# 18f45502.net
KiCad netlist of a schematic drawn in EAGLE
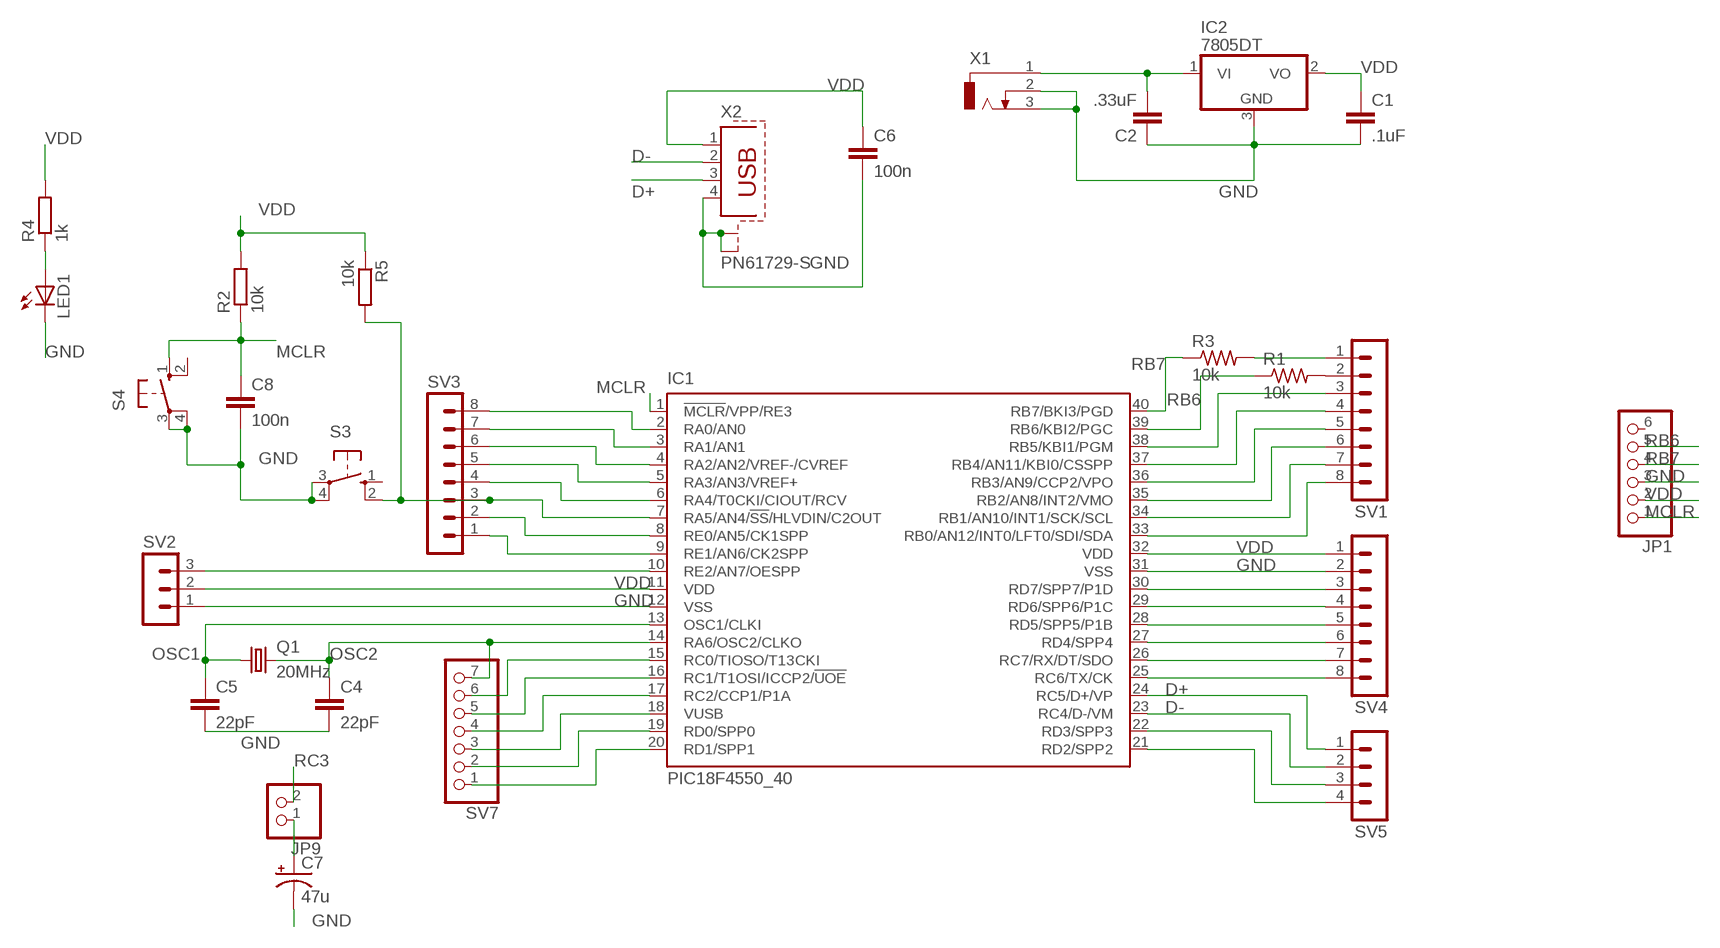
[diagram p0: schematic, sheet 1]

(export (version "E")
  (design (tool "Eeschema 10.0.6"))
  (components
    (comp (ref "C1")
      (value ".1uF")
      (footprint "eagle-import:C0805K")
      (libsource (lib "eagle-import") (part "C-EUC0805K"))
    )
    (comp (ref "C2")
      (value ".33uF")
      (footprint "eagle-import:C0805K")
      (libsource (lib "eagle-import") (part "C-EUC0805K"))
    )
    (comp (ref "C4")
      (value "22pF")
      (footprint "eagle-import:C0805K")
      (libsource (lib "eagle-import") (part "C-EUC0805K"))
    )
    (comp (ref "C5")
      (value "22pF")
      (footprint "eagle-import:C0805K")
      (libsource (lib "eagle-import") (part "C-EUC0805K"))
    )
    (comp (ref "C6")
      (value "100n")
      (footprint "eagle-import:C0805K")
      (libsource (lib "eagle-import") (part "C-EUC0805K"))
    )
    (comp (ref "C7")
      (value "47u")
      (footprint "eagle-import:TT2D5L")
      (libsource (lib "eagle-import") (part "CPOL-USTT2D5L"))
    )
    (comp (ref "C8")
      (value "100n")
      (footprint "eagle-import:C0805K")
      (libsource (lib "eagle-import") (part "C-EUC0805K"))
    )
    (comp (ref "IC1")
      (value "PIC18F4550_40")
      (footprint "eagle-import:DIL40")
      (libsource (lib "eagle-import") (part "PIC18F4_40550"))
    )
    (comp (ref "IC2")
      (value "7805DT")
      (footprint "eagle-import:TO252")
      (libsource (lib "eagle-import") (part "78DT05"))
    )
    (comp (ref "JP1")
      (value "PINHD-1X6")
      (footprint "eagle-import:1X06")
      (libsource (lib "eagle-import") (part "PINHD-1X6"))
    )
    (comp (ref "JP9")
      (value "PINHD-1X2")
      (footprint "eagle-import:1X02")
      (libsource (lib "eagle-import") (part "PINHD-1X2"))
    )
    (comp (ref "LED1")
      (value "LED3MM")
      (footprint "eagle-import:LED3MM")
      (libsource (lib "eagle-import") (part "LED3MM"))
    )
    (comp (ref "Q1")
      (value "20MHz")
      (footprint "eagle-import:HC49_S")
      (libsource (lib "eagle-import") (part "CRYSTALHC49S"))
    )
    (comp (ref "R1")
      (value "10k")
      (footprint "eagle-import:R0805")
      (libsource (lib "eagle-import") (part "R-US_R0805"))
    )
    (comp (ref "R2")
      (value "10k")
      (footprint "eagle-import:R0805")
      (libsource (lib "eagle-import") (part "R-EU_R0805"))
    )
    (comp (ref "R3")
      (value "10k")
      (footprint "eagle-import:R0805")
      (libsource (lib "eagle-import") (part "R-US_R0805"))
    )
    (comp (ref "R4")
      (value "1k")
      (footprint "eagle-import:R0805")
      (libsource (lib "eagle-import") (part "R-EU_R0805"))
    )
    (comp (ref "R5")
      (value "10k")
      (footprint "eagle-import:R0805")
      (libsource (lib "eagle-import") (part "R-EU_R0805"))
    )
    (comp (ref "S3")
      (value "10-XX")
      (footprint "eagle-import:B3F-10XX")
      (fields (field (name "MPN") "B3F-1000"))
      (libsource (lib "eagle-import") (part "10-XX"))
    )
    (comp (ref "S4")
      (value "10-XX")
      (footprint "eagle-import:B3F-10XX")
      (fields (field (name "MPN") "B3F-1000"))
      (libsource (lib "eagle-import") (part "10-XX"))
    )
    (comp (ref "SV1")
      (value "MA08-1")
      (footprint "eagle-import:MA08-1")
      (libsource (lib "eagle-import") (part "MA08-1"))
    )
    (comp (ref "SV2")
      (value "MA03-1")
      (footprint "eagle-import:MA03-1")
      (libsource (lib "eagle-import") (part "MA03-1"))
    )
    (comp (ref "SV3")
      (value "MA08-1")
      (footprint "eagle-import:MA08-1")
      (libsource (lib "eagle-import") (part "MA08-1"))
    )
    (comp (ref "SV4")
      (value "MA08-1")
      (footprint "eagle-import:MA08-1")
      (libsource (lib "eagle-import") (part "MA08-1"))
    )
    (comp (ref "SV5")
      (value "MA04-1")
      (footprint "eagle-import:MA04-1")
      (libsource (lib "eagle-import") (part "MA04-1"))
    )
    (comp (ref "SV7")
      (value "PINHD-1X7")
      (footprint "eagle-import:1X07")
      (libsource (lib "eagle-import") (part "PINHD-1X7"))
    )
    (comp (ref "X1")
      (value "DCJ0202")
      (footprint "eagle-import:DCJ0202")
      (libsource (lib "eagle-import") (part "DCJ0202"))
    )
    (comp (ref "X2")
      (value "PN61729-S")
      (footprint "eagle-import:PN61729-S")
      (libsource (lib "eagle-import") (part "PN61729-S"))
    )
  )
  (nets
    (net (code "1") (name "/D+") (class "Default")
      (node (ref "IC1") (pin "24") (pinfunction "RC5/D+/VP_24") (pintype "bidirectional"))
      (node (ref "SV5") (pin "1") (pinfunction "1_1") (pintype "passive"))
      (node (ref "X2") (pin "3") (pinfunction "3_3") (pintype "passive"))
    )
    (net (code "2") (name "/D-") (class "Default")
      (node (ref "IC1") (pin "23") (pinfunction "RC4/D-/VM_23") (pintype "bidirectional"))
      (node (ref "SV5") (pin "2") (pinfunction "2_2") (pintype "passive"))
      (node (ref "X2") (pin "2") (pinfunction "2_2") (pintype "passive"))
    )
    (net (code "3") (name "/GND") (class "Default")
      (node (ref "C1") (pin "2") (pinfunction "2_2") (pintype "passive"))
      (node (ref "C2") (pin "1") (pinfunction "1_1") (pintype "passive"))
      (node (ref "C4") (pin "2") (pinfunction "2_2") (pintype "passive"))
      (node (ref "C5") (pin "2") (pinfunction "2_2") (pintype "passive"))
      (node (ref "C6") (pin "2") (pinfunction "2_2") (pintype "passive"))
      (node (ref "C7") (pin "-") (pinfunction "-_-") (pintype "passive"))
      (node (ref "C8") (pin "2") (pinfunction "2_2") (pintype "passive"))
      (node (ref "IC1") (pin "12") (pinfunction "VSS_12") (pintype "power_in"))
      (node (ref "IC1") (pin "31") (pinfunction "VSS_31") (pintype "power_in"))
      (node (ref "IC2") (pin "3") (pinfunction "GND_3") (pintype "passive"))
      (node (ref "JP1") (pin "3") (pinfunction "3_3") (pintype "passive"))
      (node (ref "LED1") (pin "K") (pinfunction "C_K") (pintype "passive"))
      (node (ref "S3") (pin "3") (pinfunction "P_3") (pintype "passive"))
      (node (ref "S3") (pin "4") (pinfunction "P1_4") (pintype "passive"))
      (node (ref "S4") (pin "3") (pinfunction "P_3") (pintype "passive"))
      (node (ref "S4") (pin "4") (pinfunction "P1_4") (pintype "passive"))
      (node (ref "SV2") (pin "1") (pinfunction "1_1") (pintype "passive"))
      (node (ref "SV4") (pin "2") (pinfunction "2_2") (pintype "passive"))
      (node (ref "X1") (pin "2") (pinfunction "2_2") (pintype "passive"))
      (node (ref "X1") (pin "3") (pinfunction "3_3") (pintype "passive"))
      (node (ref "X2") (pin "4") (pinfunction "4_4") (pintype "passive"))
      (node (ref "X2") (pin "S1") (pinfunction "S1_S1") (pintype "passive"))
      (node (ref "X2") (pin "S2") (pinfunction "S2_S2") (pintype "passive"))
    )
    (net (code "4") (name "/MCLR") (class "Default")
      (node (ref "C8") (pin "1") (pinfunction "1_1") (pintype "passive"))
      (node (ref "IC1") (pin "1") (pinfunction "~{MCLR}/VPP/RE3_1") (pintype "input"))
      (node (ref "JP1") (pin "1") (pinfunction "1_1") (pintype "passive"))
      (node (ref "R2") (pin "1") (pinfunction "1_1") (pintype "passive"))
      (node (ref "S4") (pin "1") (pinfunction "S_1") (pintype "passive"))
    )
    (net (code "5") (name "/OSC1") (class "Default")
      (node (ref "C5") (pin "1") (pinfunction "1_1") (pintype "passive"))
      (node (ref "IC1") (pin "13") (pinfunction "OSC1/CLKI_13") (pintype "input"))
      (node (ref "Q1") (pin "1") (pinfunction "1_1") (pintype "passive"))
    )
    (net (code "6") (name "/OSC2") (class "Default")
      (node (ref "C4") (pin "1") (pinfunction "1_1") (pintype "passive"))
      (node (ref "IC1") (pin "14") (pinfunction "RA6/OSC2/CLKO_14") (pintype "output"))
      (node (ref "Q1") (pin "2") (pinfunction "2_2") (pintype "passive"))
      (node (ref "SV7") (pin "7") (pinfunction "7_7") (pintype "passive"))
    )
    (net (code "7") (name "/RB6") (class "Default")
      (node (ref "IC1") (pin "39") (pinfunction "RB6/KBI2/PGC_39") (pintype "bidirectional"))
      (node (ref "JP1") (pin "5") (pinfunction "5_5") (pintype "passive"))
      (node (ref "R1") (pin "1") (pinfunction "1_1") (pintype "passive"))
    )
    (net (code "8") (name "/RB7") (class "Default")
      (node (ref "IC1") (pin "40") (pinfunction "RB7/BKI3/PGD_40") (pintype "bidirectional"))
      (node (ref "JP1") (pin "4") (pinfunction "4_4") (pintype "passive"))
      (node (ref "R3") (pin "1") (pinfunction "1_1") (pintype "passive"))
    )
    (net (code "9") (name "/RC3") (class "Default")
      (node (ref "IC1") (pin "18") (pinfunction "VUSB_18") (pintype "bidirectional"))
      (node (ref "JP9") (pin "2") (pinfunction "2_2") (pintype "passive"))
      (node (ref "SV7") (pin "3") (pinfunction "3_3") (pintype "passive"))
    )
    (net (code "10") (name "/VDD") (class "Default")
      (node (ref "C1") (pin "1") (pinfunction "1_1") (pintype "passive"))
      (node (ref "C6") (pin "1") (pinfunction "1_1") (pintype "passive"))
      (node (ref "IC1") (pin "11") (pinfunction "VDD_11") (pintype "power_in"))
      (node (ref "IC1") (pin "32") (pinfunction "VDD_32") (pintype "power_in"))
      (node (ref "IC2") (pin "2") (pinfunction "VO_2") (pintype "passive"))
      (node (ref "JP1") (pin "2") (pinfunction "2_2") (pintype "passive"))
      (node (ref "R2") (pin "2") (pinfunction "2_2") (pintype "passive"))
      (node (ref "R4") (pin "2") (pinfunction "2_2") (pintype "passive"))
      (node (ref "R5") (pin "1") (pinfunction "1_1") (pintype "passive"))
      (node (ref "SV2") (pin "2") (pinfunction "2_2") (pintype "passive"))
      (node (ref "SV4") (pin "1") (pinfunction "1_1") (pintype "passive"))
      (node (ref "X2") (pin "1") (pinfunction "1_1") (pintype "passive"))
    )
    (net (code "11") (name "Net-(C7-Pad+)") (class "Default")
      (node (ref "C7") (pin "+") (pinfunction "+_+") (pintype "passive"))
      (node (ref "JP9") (pin "1") (pinfunction "1_1") (pintype "passive"))
    )
    (net (code "12") (name "Net-(IC1-RA0{slash}AN0)") (class "Default")
      (node (ref "IC1") (pin "2") (pinfunction "RA0/AN0_2") (pintype "bidirectional"))
      (node (ref "SV3") (pin "8") (pinfunction "8_8") (pintype "passive"))
    )
    (net (code "13") (name "Net-(IC1-RA1{slash}AN1)") (class "Default")
      (node (ref "IC1") (pin "3") (pinfunction "RA1/AN1_3") (pintype "bidirectional"))
      (node (ref "SV3") (pin "7") (pinfunction "7_7") (pintype "passive"))
    )
    (net (code "14") (name "Net-(IC1-RA2{slash}AN2{slash}VREF-{slash}CVREF)") (class "Default")
      (node (ref "IC1") (pin "4") (pinfunction "RA2/AN2/VREF-/CVREF_4") (pintype "bidirectional"))
      (node (ref "SV3") (pin "6") (pinfunction "6_6") (pintype "passive"))
    )
    (net (code "15") (name "Net-(IC1-RA3{slash}AN3{slash}VREF+)") (class "Default")
      (node (ref "IC1") (pin "5") (pinfunction "RA3/AN3/VREF+_5") (pintype "bidirectional"))
      (node (ref "SV3") (pin "5") (pinfunction "5_5") (pintype "passive"))
    )
    (net (code "16") (name "Net-(IC1-RA4{slash}T0CKI{slash}CIOUT{slash}RCV)") (class "Default")
      (node (ref "IC1") (pin "6") (pinfunction "RA4/T0CKI/CIOUT/RCV_6") (pintype "bidirectional"))
      (node (ref "SV3") (pin "4") (pinfunction "4_4") (pintype "passive"))
    )
    (net (code "17") (name "Net-(IC1-RA5{slash}AN4{slash}~{SS}{slash}HLVDIN{slash}C2OUT)") (class "Default")
      (node (ref "IC1") (pin "7") (pinfunction "RA5/AN4/~{SS}/HLVDIN/C2OUT_7") (pintype "bidirectional"))
      (node (ref "R5") (pin "2") (pinfunction "2_2") (pintype "passive"))
      (node (ref "S3") (pin "2") (pinfunction "S1_2") (pintype "passive"))
      (node (ref "SV3") (pin "3") (pinfunction "3_3") (pintype "passive"))
    )
    (net (code "18") (name "Net-(IC1-RB0{slash}AN12{slash}INT0{slash}LFT0{slash}SDI{slash}SDA)") (class "Default")
      (node (ref "IC1") (pin "33") (pinfunction "RB0/AN12/INT0/LFT0/SDI/SDA_33") (pintype "bidirectional"))
      (node (ref "SV1") (pin "8") (pinfunction "8_8") (pintype "passive"))
    )
    (net (code "19") (name "Net-(IC1-RB1{slash}AN10{slash}INT1{slash}SCK{slash}SCL)") (class "Default")
      (node (ref "IC1") (pin "34") (pinfunction "RB1/AN10/INT1/SCK/SCL_34") (pintype "bidirectional"))
      (node (ref "SV1") (pin "7") (pinfunction "7_7") (pintype "passive"))
    )
    (net (code "20") (name "Net-(IC1-RB2{slash}AN8{slash}INT2{slash}VMO)") (class "Default")
      (node (ref "IC1") (pin "35") (pinfunction "RB2/AN8/INT2/VMO_35") (pintype "bidirectional"))
      (node (ref "SV1") (pin "6") (pinfunction "6_6") (pintype "passive"))
    )
    (net (code "21") (name "Net-(IC1-RB3{slash}AN9{slash}CCP2{slash}VPO)") (class "Default")
      (node (ref "IC1") (pin "36") (pinfunction "RB3/AN9/CCP2/VPO_36") (pintype "bidirectional"))
      (node (ref "SV1") (pin "5") (pinfunction "5_5") (pintype "passive"))
    )
    (net (code "22") (name "Net-(IC1-RB4{slash}AN11{slash}KBI0{slash}CSSPP)") (class "Default")
      (node (ref "IC1") (pin "37") (pinfunction "RB4/AN11/KBI0/CSSPP_37") (pintype "bidirectional"))
      (node (ref "SV1") (pin "4") (pinfunction "4_4") (pintype "passive"))
    )
    (net (code "23") (name "Net-(IC1-RB5{slash}KBI1{slash}PGM)") (class "Default")
      (node (ref "IC1") (pin "38") (pinfunction "RB5/KBI1/PGM_38") (pintype "bidirectional"))
      (node (ref "SV1") (pin "3") (pinfunction "3_3") (pintype "passive"))
    )
    (net (code "24") (name "Net-(IC1-RC0{slash}TIOSO{slash}T13CKI)") (class "Default")
      (node (ref "IC1") (pin "15") (pinfunction "RC0/TIOSO/T13CKI_15") (pintype "bidirectional"))
      (node (ref "SV7") (pin "6") (pinfunction "6_6") (pintype "passive"))
    )
    (net (code "25") (name "Net-(IC1-RC1{slash}T1OSI{slash}ICCP2{slash}~{UOE})") (class "Default")
      (node (ref "IC1") (pin "16") (pinfunction "RC1/T1OSI/ICCP2/~{UOE}_16") (pintype "bidirectional"))
      (node (ref "SV7") (pin "5") (pinfunction "5_5") (pintype "passive"))
    )
    (net (code "26") (name "Net-(IC1-RC2{slash}CCP1{slash}P1A)") (class "Default")
      (node (ref "IC1") (pin "17") (pinfunction "RC2/CCP1/P1A_17") (pintype "bidirectional"))
      (node (ref "SV7") (pin "4") (pinfunction "4_4") (pintype "passive"))
    )
    (net (code "27") (name "Net-(IC1-RC6{slash}TX{slash}CK)") (class "Default")
      (node (ref "IC1") (pin "25") (pinfunction "RC6/TX/CK_25") (pintype "bidirectional"))
      (node (ref "SV4") (pin "8") (pinfunction "8_8") (pintype "passive"))
    )
    (net (code "28") (name "Net-(IC1-RC7{slash}RX{slash}DT{slash}SDO)") (class "Default")
      (node (ref "IC1") (pin "26") (pinfunction "RC7/RX/DT/SDO_26") (pintype "bidirectional"))
      (node (ref "SV4") (pin "7") (pinfunction "7_7") (pintype "passive"))
    )
    (net (code "29") (name "Net-(IC1-RD0{slash}SPP0)") (class "Default")
      (node (ref "IC1") (pin "19") (pinfunction "RD0/SPP0_19") (pintype "bidirectional"))
      (node (ref "SV7") (pin "2") (pinfunction "2_2") (pintype "passive"))
    )
    (net (code "30") (name "Net-(IC1-RD1{slash}SPP1)") (class "Default")
      (node (ref "IC1") (pin "20") (pinfunction "RD1/SPP1_20") (pintype "bidirectional"))
      (node (ref "SV7") (pin "1") (pinfunction "1_1") (pintype "passive"))
    )
    (net (code "31") (name "Net-(IC1-RD2{slash}SPP2)") (class "Default")
      (node (ref "IC1") (pin "21") (pinfunction "RD2/SPP2_21") (pintype "bidirectional"))
      (node (ref "SV5") (pin "4") (pinfunction "4_4") (pintype "passive"))
    )
    (net (code "32") (name "Net-(IC1-RD3{slash}SPP3)") (class "Default")
      (node (ref "IC1") (pin "22") (pinfunction "RD3/SPP3_22") (pintype "bidirectional"))
      (node (ref "SV5") (pin "3") (pinfunction "3_3") (pintype "passive"))
    )
    (net (code "33") (name "Net-(IC1-RD4{slash}SPP4)") (class "Default")
      (node (ref "IC1") (pin "27") (pinfunction "RD4/SPP4_27") (pintype "bidirectional"))
      (node (ref "SV4") (pin "6") (pinfunction "6_6") (pintype "passive"))
    )
    (net (code "34") (name "Net-(IC1-RD5{slash}SPP5{slash}P1B)") (class "Default")
      (node (ref "IC1") (pin "28") (pinfunction "RD5/SPP5/P1B_28") (pintype "bidirectional"))
      (node (ref "SV4") (pin "5") (pinfunction "5_5") (pintype "passive"))
    )
    (net (code "35") (name "Net-(IC1-RD6{slash}SPP6{slash}P1C)") (class "Default")
      (node (ref "IC1") (pin "29") (pinfunction "RD6/SPP6/P1C_29") (pintype "bidirectional"))
      (node (ref "SV4") (pin "4") (pinfunction "4_4") (pintype "passive"))
    )
    (net (code "36") (name "Net-(IC1-RD7{slash}SPP7{slash}P1D)") (class "Default")
      (node (ref "IC1") (pin "30") (pinfunction "RD7/SPP7/P1D_30") (pintype "bidirectional"))
      (node (ref "SV4") (pin "3") (pinfunction "3_3") (pintype "passive"))
    )
    (net (code "37") (name "Net-(IC1-RE0{slash}AN5{slash}CK1SPP)") (class "Default")
      (node (ref "IC1") (pin "8") (pinfunction "RE0/AN5/CK1SPP_8") (pintype "bidirectional"))
      (node (ref "SV3") (pin "2") (pinfunction "2_2") (pintype "passive"))
    )
    (net (code "38") (name "Net-(IC1-RE1{slash}AN6{slash}CK2SPP)") (class "Default")
      (node (ref "IC1") (pin "9") (pinfunction "RE1/AN6/CK2SPP_9") (pintype "bidirectional"))
      (node (ref "SV3") (pin "1") (pinfunction "1_1") (pintype "passive"))
    )
    (net (code "39") (name "Net-(IC1-RE2{slash}AN7{slash}OESPP)") (class "Default")
      (node (ref "IC1") (pin "10") (pinfunction "RE2/AN7/OESPP_10") (pintype "bidirectional"))
      (node (ref "SV2") (pin "3") (pinfunction "3_3") (pintype "passive"))
    )
    (net (code "40") (name "Net-(IC2-VI)") (class "Default")
      (node (ref "C2") (pin "2") (pinfunction "2_2") (pintype "passive"))
      (node (ref "IC2") (pin "1") (pinfunction "VI_1") (pintype "input"))
      (node (ref "X1") (pin "1") (pinfunction "1_1") (pintype "passive"))
    )
    (net (code "41") (name "Net-(LED1-PadA)") (class "Default")
      (node (ref "LED1") (pin "A") (pinfunction "A_A") (pintype "passive"))
      (node (ref "R4") (pin "1") (pinfunction "1_1") (pintype "passive"))
    )
    (net (code "42") (name "Net-(R1-Pad2)") (class "Default")
      (node (ref "R1") (pin "2") (pinfunction "2_2") (pintype "passive"))
      (node (ref "SV1") (pin "2") (pinfunction "2_2") (pintype "passive"))
    )
    (net (code "43") (name "Net-(R3-Pad2)") (class "Default")
      (node (ref "R3") (pin "2") (pinfunction "2_2") (pintype "passive"))
      (node (ref "SV1") (pin "1") (pinfunction "1_1") (pintype "passive"))
    )
    (net (code "44") (name "unconnected-(JP1-Pad6)") (class "Default")
      (node (ref "JP1") (pin "6") (pinfunction "6_6") (pintype "passive"))
    )
    (net (code "45") (name "unconnected-(S3-S-Pad1)") (class "Default")
      (node (ref "S3") (pin "1") (pinfunction "S_1") (pintype "passive"))
    )
    (net (code "46") (name "unconnected-(S4-S1-Pad2)") (class "Default")
      (node (ref "S4") (pin "2") (pinfunction "S1_2") (pintype "passive"))
    )
  )
)
